# BinaryClock_Control.net
KiCad netlist of a schematic drawn in Altium Designer
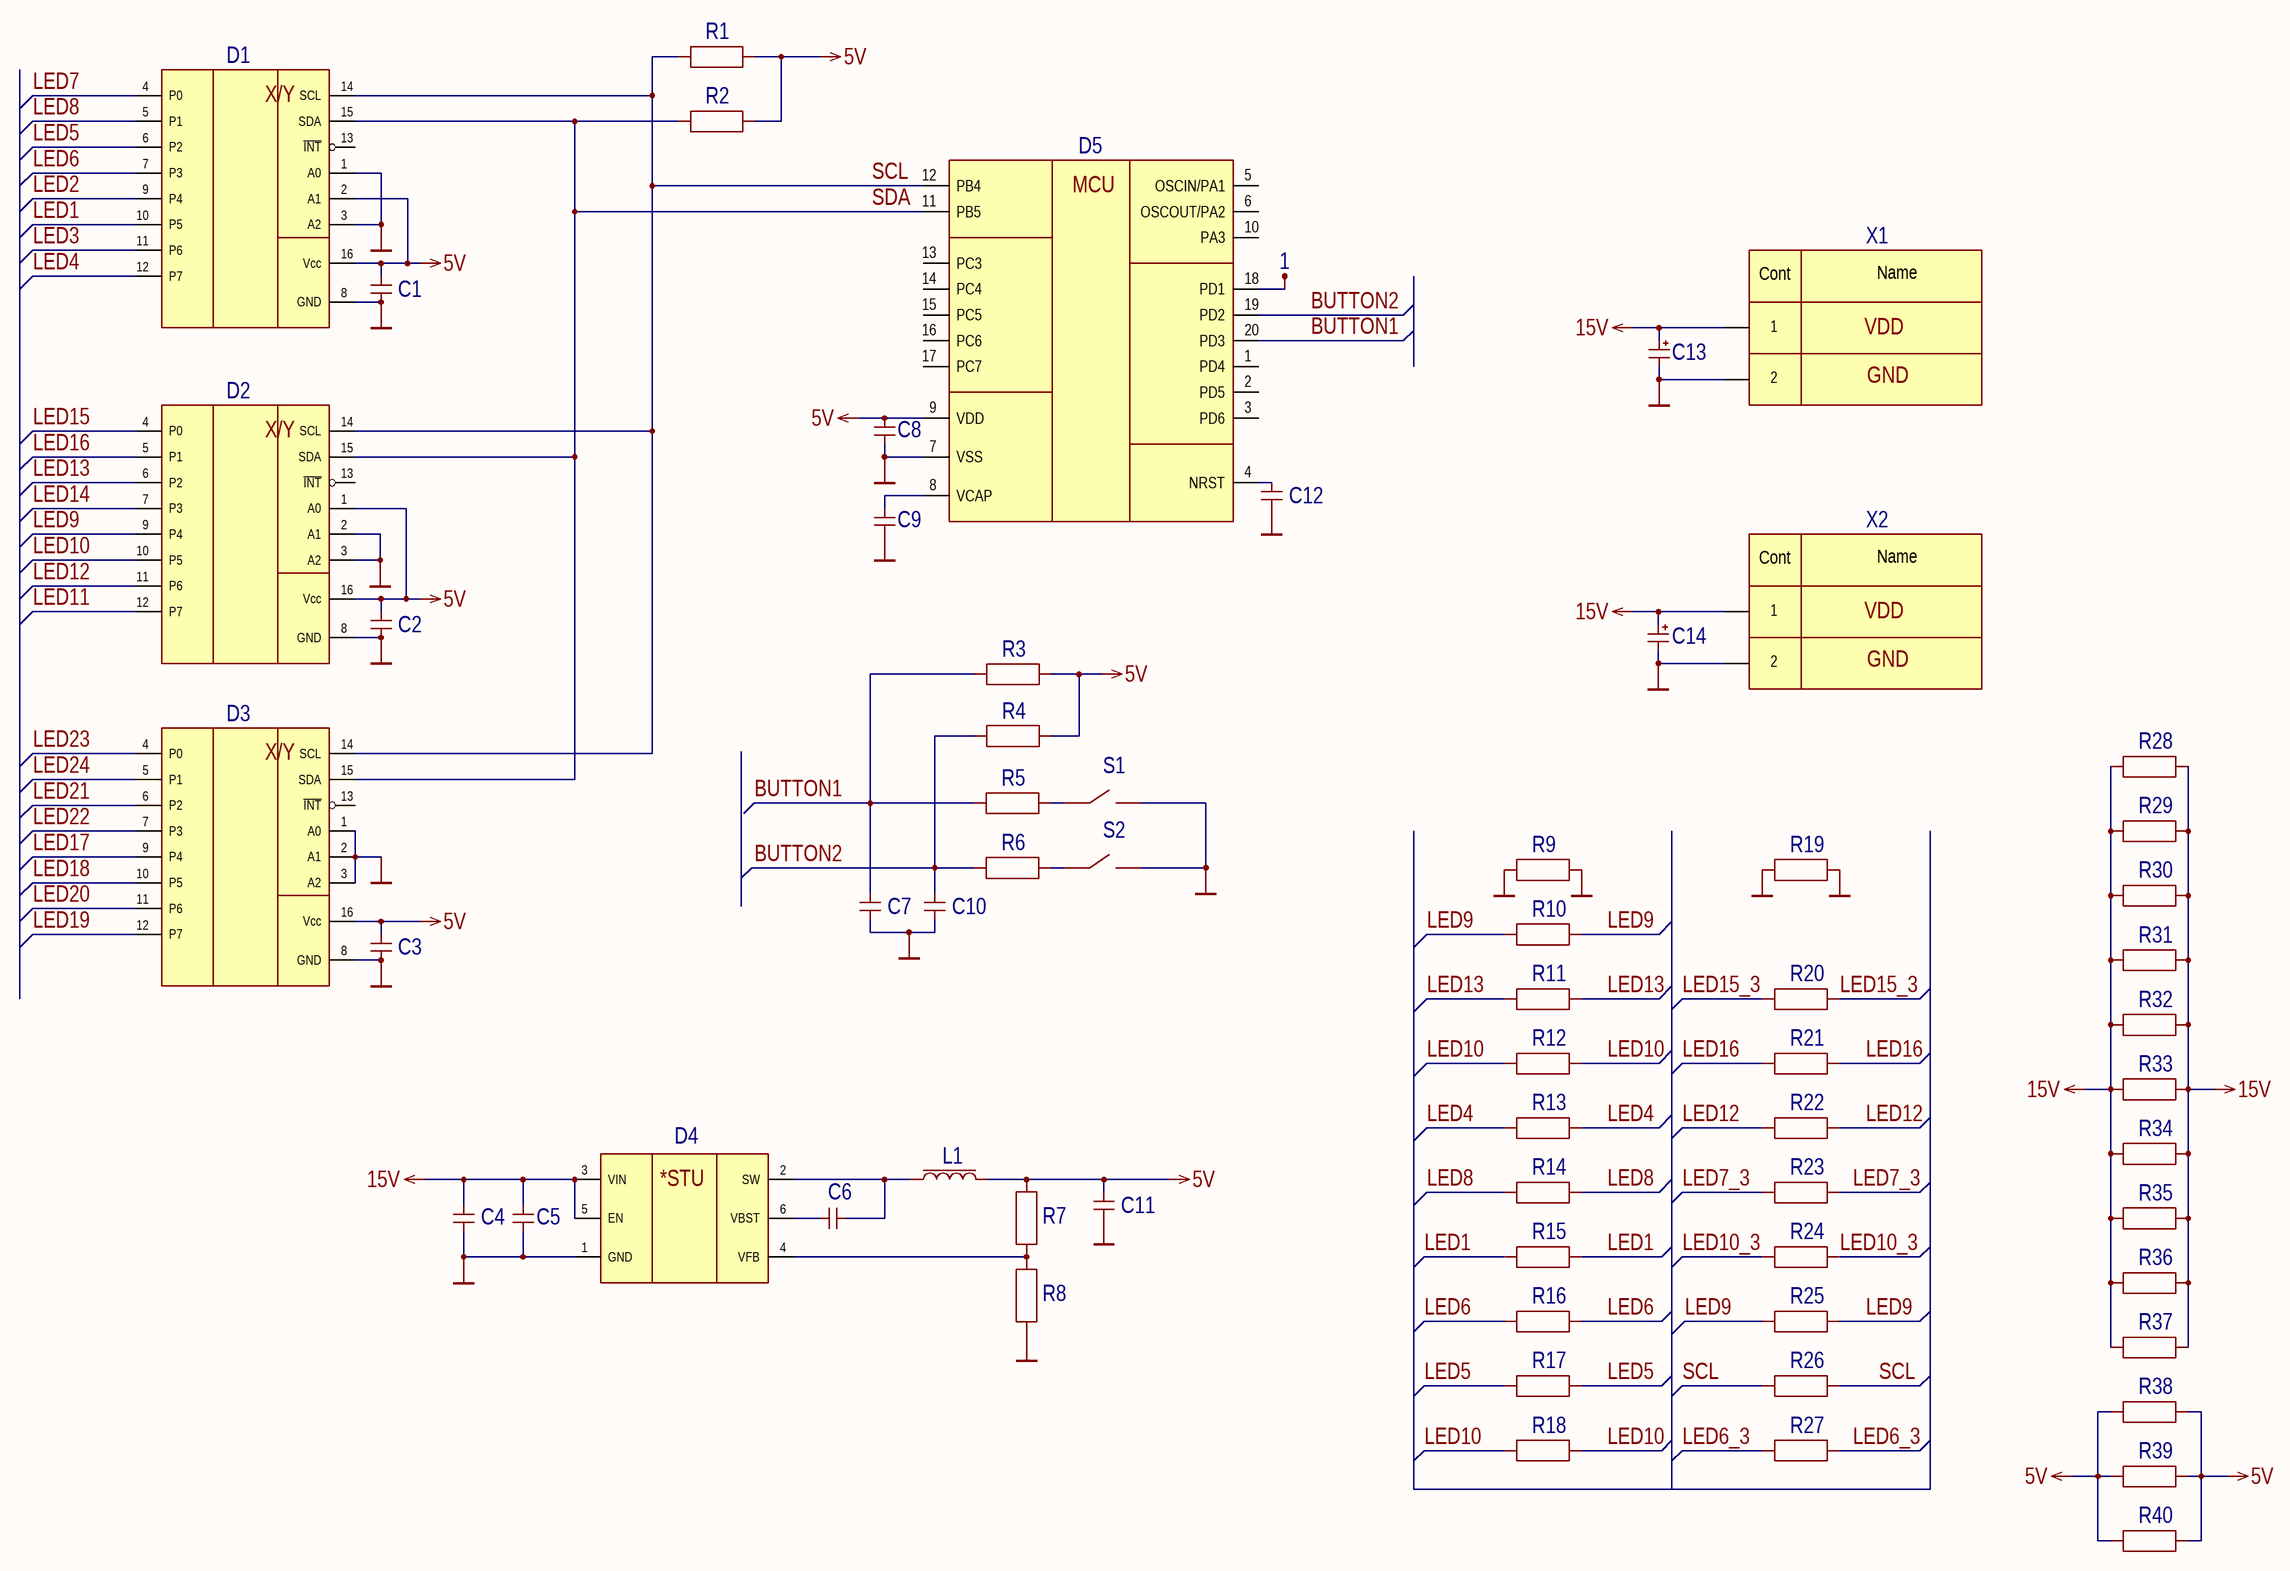
[diagram p0: BinaryClock_Control.SchDoc]

(export (version "E")
  (design (tool "Eeschema 10.0.6"))
  (components
    (comp (ref "1") (value "Point") (footprint "point") (libsource (lib "Passive,Diodes") (part "Point")))
    (comp (ref "C1")
      (value "0805-16 V-X7R-0.1uF±10 %")
      (footprint "SMD-0805C")
      (description "Capacitor")
      (fields (field (name "MANUFACTURER") "Murata"))
      (libsource (lib "Passive,Diodes") (part "Cap"))
    )
    (comp (ref "C2")
      (value "0805-16 V-X7R-0.1uF±10 %")
      (footprint "SMD-0805C")
      (description "Capacitor")
      (fields (field (name "MANUFACTURER") "Murata"))
      (libsource (lib "Passive,Diodes") (part "Cap"))
    )
    (comp (ref "C3")
      (value "0805-16 V-X7R-0.1uF±10 %")
      (footprint "SMD-0805C")
      (description "Capacitor")
      (fields (field (name "MANUFACTURER") "Murata"))
      (libsource (lib "Passive,Diodes") (part "Cap"))
    )
    (comp (ref "C4")
      (value "0805-25 V-X5R-10uF±10 %")
      (footprint "SMD-0805C")
      (description "Capacitor")
      (libsource (lib "Passive,Diodes") (part "Cap"))
    )
    (comp (ref "C5")
      (value "0805-50 V-X7R-0.1uF±10 %")
      (footprint "SMD-0805C")
      (description "Capacitor")
      (libsource (lib "Passive,Diodes") (part "Cap"))
    )
    (comp (ref "C6")
      (value "0805-16 V-X7R-0.1uF±10 %")
      (footprint "SMD-0805C")
      (description "Capacitor")
      (fields (field (name "MANUFACTURER") "Murata"))
      (libsource (lib "Passive,Diodes") (part "Cap"))
    )
    (comp (ref "C7")
      (value "0805-16 V-X7R-0.1uF±10 %")
      (footprint "SMD-0805C")
      (description "Capacitor")
      (fields (field (name "MANUFACTURER") "Murata"))
      (libsource (lib "Passive,Diodes") (part "Cap"))
    )
    (comp (ref "C8")
      (value "0805-16 V-X7R-0.1uF±10 %")
      (footprint "SMD-0805C")
      (description "Capacitor")
      (fields (field (name "MANUFACTURER") "Murata"))
      (libsource (lib "Passive,Diodes") (part "Cap"))
    )
    (comp (ref "C9")
      (value "0805-16 V-X7R-1uF±10 %")
      (footprint "SMD-0805C")
      (description "Capacitor")
      (fields (field (name "MANUFACTURER") "Murata"))
      (libsource (lib "Passive,Diodes") (part "Cap"))
    )
    (comp (ref "C10")
      (value "0805-16 V-X7R-0.1uF±10 %")
      (footprint "SMD-0805C")
      (description "Capacitor")
      (fields (field (name "MANUFACTURER") "Murata"))
      (libsource (lib "Passive,Diodes") (part "Cap"))
    )
    (comp (ref "C11")
      (value "1206-16 V-X7R-22uF±10 %")
      (footprint "SMD-1206C")
      (description "Capacitor")
      (libsource (lib "Passive,Diodes") (part "Cap"))
    )
    (comp (ref "C12")
      (value "0805-16 V-X7R-0.1uF±10 %")
      (footprint "SMD-0805C")
      (description "Capacitor")
      (fields (field (name "MANUFACTURER") "Murata"))
      (libsource (lib "Passive,Diodes") (part "Cap"))
    )
    (comp (ref "C13")
      (value "10x10.5-50 V-100 uF±20 %")
      (footprint "CAP_10x10.5")
      (description "Electrolytic capacitor")
      (libsource (lib "Passive,Diodes") (part "Cap_el"))
    )
    (comp (ref "C14")
      (value "10x10.5-50 V-100 uF±20 %")
      (footprint "CAP_10x10.5")
      (description "Electrolytic capacitor")
      (libsource (lib "Passive,Diodes") (part "Cap_el"))
    )
    (comp (ref "D1")
      (value "PCF8574T/3.512")
      (footprint "SO-16")
      (description "Remote 8-bit I/O expander for I2C bus")
      (fields (field (name "MANUFACTURER") "NXP"))
      (libsource (lib "Devices") (part "PCF8574"))
    )
    (comp (ref "D2")
      (value "PCF8574T/3.512")
      (footprint "SO-16")
      (description "Remote 8-bit I/O expander for I2C bus")
      (fields (field (name "MANUFACTURER") "NXP"))
      (libsource (lib "Devices") (part "PCF8574"))
    )
    (comp (ref "D3")
      (value "PCF8574T/3.512")
      (footprint "SO-16")
      (description "Remote 8-bit I/O expander for I2C bus")
      (fields (field (name "MANUFACTURER") "NXP"))
      (libsource (lib "Devices") (part "PCF8574"))
    )
    (comp (ref "D4")
      (value "TPS562200DDCT")
      (footprint "SOT23-6_M")
      (description "4.5-V To 17-V Input, 2-A, 3-A Synchronous Step-Down Voltage Regulator")
      (fields (field (name "MANUFACTURER") "Texas Instruments"))
      (libsource (lib "Devices") (part "TPS562200"))
    )
    (comp (ref "D5")
      (value "STM8S103F3P6")
      (footprint "TSSOP-20")
      (fields (field (name "MANUFACTURER") "STMicroelectronics"))
      (libsource (lib "Devices") (part "STM8S103FxP"))
    )
    (comp (ref "L1")
      (value "NLCV32T-4R7M-EF")
      (footprint "1210_M")
      (description "Inductor")
      (fields (field (name "MANUFACTURER") "TDK"))
      (libsource (lib "Passive,Diodes") (part "Inductor"))
    )
    (comp (ref "R1")
      (value "0805±5 %-10 kOhm")
      (footprint "SMD-0805-RES")
      (description "Resistor")
      (libsource (lib "Passive,Diodes") (part "Res"))
    )
    (comp (ref "R2")
      (value "0805±5 %-10 kOhm")
      (footprint "SMD-0805-RES")
      (description "Resistor")
      (libsource (lib "Passive,Diodes") (part "Res"))
    )
    (comp (ref "R3")
      (value "0805±5 %-10 kOhm")
      (footprint "SMD-0805-RES")
      (description "Resistor")
      (libsource (lib "Passive,Diodes") (part "Res"))
    )
    (comp (ref "R4")
      (value "0805±5 %-10 kOhm")
      (footprint "SMD-0805-RES")
      (description "Resistor")
      (libsource (lib "Passive,Diodes") (part "Res"))
    )
    (comp (ref "R5")
      (value "0805±5 %-100 Ohm")
      (footprint "SMD-0805-RES")
      (description "Resistor")
      (libsource (lib "Passive,Diodes") (part "Res"))
    )
    (comp (ref "R6")
      (value "0805±5 %-100 Ohm")
      (footprint "SMD-0805-RES")
      (description "Resistor")
      (libsource (lib "Passive,Diodes") (part "Res"))
    )
    (comp (ref "R7")
      (value "0805±1 %-110 kOhm")
      (footprint "SMD-0805-RES")
      (description "Resistor")
      (libsource (lib "Passive,Diodes") (part "Res"))
    )
    (comp (ref "R8")
      (value "0805±1 %-20 kOhm")
      (footprint "SMD-0805-RES")
      (description "Resistor")
      (libsource (lib "Passive,Diodes") (part "Res"))
    )
    (comp (ref "R9")
      (value "1206±5 %-0 Ohm")
      (footprint "R1206")
      (description "Resistor")
      (libsource (lib "Passive,Diodes") (part "Res"))
    )
    (comp (ref "R10")
      (value "1206±5 %-0 Ohm")
      (footprint "R1206")
      (description "Resistor")
      (libsource (lib "Passive,Diodes") (part "Res"))
    )
    (comp (ref "R11")
      (value "1206±5 %-0 Ohm")
      (footprint "R1206")
      (description "Resistor")
      (libsource (lib "Passive,Diodes") (part "Res"))
    )
    (comp (ref "R12")
      (value "1206±5 %-0 Ohm")
      (footprint "R1206")
      (description "Resistor")
      (libsource (lib "Passive,Diodes") (part "Res"))
    )
    (comp (ref "R13")
      (value "1206±5 %-0 Ohm")
      (footprint "R1206")
      (description "Resistor")
      (libsource (lib "Passive,Diodes") (part "Res"))
    )
    (comp (ref "R14")
      (value "1206±5 %-0 Ohm")
      (footprint "R1206")
      (description "Resistor")
      (libsource (lib "Passive,Diodes") (part "Res"))
    )
    (comp (ref "R15")
      (value "1206±5 %-0 Ohm")
      (footprint "R1206")
      (description "Resistor")
      (libsource (lib "Passive,Diodes") (part "Res"))
    )
    (comp (ref "R16")
      (value "1206±5 %-0 Ohm")
      (footprint "R1206")
      (description "Resistor")
      (libsource (lib "Passive,Diodes") (part "Res"))
    )
    (comp (ref "R17")
      (value "1206±5 %-0 Ohm")
      (footprint "R1206")
      (description "Resistor")
      (libsource (lib "Passive,Diodes") (part "Res"))
    )
    (comp (ref "R18")
      (value "1206±5 %-0 Ohm")
      (footprint "R1206")
      (description "Resistor")
      (libsource (lib "Passive,Diodes") (part "Res"))
    )
    (comp (ref "R19")
      (value "1206±5 %-0 Ohm")
      (footprint "R1206")
      (description "Resistor")
      (libsource (lib "Passive,Diodes") (part "Res"))
    )
    (comp (ref "R20")
      (value "1206±5 %-0 Ohm")
      (footprint "R1206")
      (description "Resistor")
      (libsource (lib "Passive,Diodes") (part "Res"))
    )
    (comp (ref "R21")
      (value "1206±5 %-0 Ohm")
      (footprint "R1206")
      (description "Resistor")
      (libsource (lib "Passive,Diodes") (part "Res"))
    )
    (comp (ref "R22")
      (value "1206±5 %-0 Ohm")
      (footprint "R1206")
      (description "Resistor")
      (libsource (lib "Passive,Diodes") (part "Res"))
    )
    (comp (ref "R23")
      (value "1206±5 %-0 Ohm")
      (footprint "R1206")
      (description "Resistor")
      (libsource (lib "Passive,Diodes") (part "Res"))
    )
    (comp (ref "R24")
      (value "1206±5 %-0 Ohm")
      (footprint "R1206")
      (description "Resistor")
      (libsource (lib "Passive,Diodes") (part "Res"))
    )
    (comp (ref "R25")
      (value "1206±5 %-0 Ohm")
      (footprint "R1206")
      (description "Resistor")
      (libsource (lib "Passive,Diodes") (part "Res"))
    )
    (comp (ref "R26")
      (value "1206±5 %-0 Ohm")
      (footprint "R1206")
      (description "Resistor")
      (libsource (lib "Passive,Diodes") (part "Res"))
    )
    (comp (ref "R27")
      (value "1206±5 %-0 Ohm")
      (footprint "R1206")
      (description "Resistor")
      (libsource (lib "Passive,Diodes") (part "Res"))
    )
    (comp (ref "R28")
      (value "1206±5 %-0 Ohm")
      (footprint "R1206")
      (description "Resistor")
      (libsource (lib "Passive,Diodes") (part "Res"))
    )
    (comp (ref "R29")
      (value "1206±5 %-0 Ohm")
      (footprint "R1206")
      (description "Resistor")
      (libsource (lib "Passive,Diodes") (part "Res"))
    )
    (comp (ref "R30")
      (value "1206±5 %-0 Ohm")
      (footprint "R1206")
      (description "Resistor")
      (libsource (lib "Passive,Diodes") (part "Res"))
    )
    (comp (ref "R31")
      (value "1206±5 %-0 Ohm")
      (footprint "R1206")
      (description "Resistor")
      (libsource (lib "Passive,Diodes") (part "Res"))
    )
    (comp (ref "R32")
      (value "1206±5 %-0 Ohm")
      (footprint "R1206")
      (description "Resistor")
      (libsource (lib "Passive,Diodes") (part "Res"))
    )
    (comp (ref "R33")
      (value "1206±5 %-0 Ohm")
      (footprint "R1206")
      (description "Resistor")
      (libsource (lib "Passive,Diodes") (part "Res"))
    )
    (comp (ref "R34")
      (value "1206±5 %-0 Ohm")
      (footprint "R1206")
      (description "Resistor")
      (libsource (lib "Passive,Diodes") (part "Res"))
    )
    (comp (ref "R35")
      (value "1206±5 %-0 Ohm")
      (footprint "R1206")
      (description "Resistor")
      (libsource (lib "Passive,Diodes") (part "Res"))
    )
    (comp (ref "R36")
      (value "1206±5 %-0 Ohm")
      (footprint "R1206")
      (description "Resistor")
      (libsource (lib "Passive,Diodes") (part "Res"))
    )
    (comp (ref "R37")
      (value "1206±5 %-0 Ohm")
      (footprint "R1206")
      (description "Resistor")
      (libsource (lib "Passive,Diodes") (part "Res"))
    )
    (comp (ref "R38")
      (value "1206±5 %-0 Ohm")
      (footprint "R1206")
      (description "Resistor")
      (libsource (lib "Passive,Diodes") (part "Res"))
    )
    (comp (ref "R39")
      (value "1206±5 %-0 Ohm")
      (footprint "R1206")
      (description "Resistor")
      (libsource (lib "Passive,Diodes") (part "Res"))
    )
    (comp (ref "R40")
      (value "1206±5 %-0 Ohm")
      (footprint "R1206")
      (description "Resistor")
      (libsource (lib "Passive,Diodes") (part "Res"))
    )
    (comp (ref "S1")
      (value "1243SHIM-160G-G")
      (footprint "1243S")
      (description "Tact button SPST")
      (fields (field (name "MANUFACTURER") "Switronic"))
      (libsource (lib "Connectors") (part "button"))
    )
    (comp (ref "S2")
      (value "1243SHIM-160G-G")
      (footprint "1243S")
      (description "Tact button SPST")
      (fields (field (name "MANUFACTURER") "Switronic"))
      (libsource (lib "Connectors") (part "button"))
    )
    (comp (ref "X1")
      (value "DC-005-5A-2.5-SMT")
      (footprint "PJ_2.5MM_SMT")
      (description "Power jack 2.5 mm SMT connector")
      (libsource (lib "Connectors") (part "Power_Jack_SMT_2.5mm"))
    )
    (comp (ref "X2")
      (value "DC-005-5A-2.5-SMT")
      (footprint "PJ_2.5MM_SMT")
      (description "Power jack 2.5 mm SMT connector")
      (libsource (lib "Connectors") (part "Power_Jack_SMT_2.5mm"))
    )
  )
  (nets
    (net (code "1") (name "/BUTTON1") (class "Default")
      (node (ref "C7") (pin "2") (pinfunction "2_2") (pintype "passive"))
      (node (ref "D5") (pin "20") (pinfunction "PD3_20") (pintype "passive"))
      (node (ref "R3") (pin "1") (pinfunction "1_1") (pintype "passive"))
      (node (ref "R5") (pin "1") (pinfunction "1_1") (pintype "passive"))
    )
    (net (code "2") (name "/BUTTON2") (class "Default")
      (node (ref "C10") (pin "2") (pinfunction "2_2") (pintype "passive"))
      (node (ref "D5") (pin "19") (pinfunction "PD2_19") (pintype "passive"))
      (node (ref "R4") (pin "1") (pinfunction "1_1") (pintype "passive"))
      (node (ref "R6") (pin "1") (pinfunction "1_1") (pintype "passive"))
    )
    (net (code "3") (name "/LED1") (class "Default")
      (node (ref "D1") (pin "10") (pinfunction "P5_10") (pintype "passive"))
      (node (ref "R15") (pin "1") (pinfunction "1_1") (pintype "passive"))
      (node (ref "R15") (pin "2") (pinfunction "2_2") (pintype "passive"))
    )
    (net (code "4") (name "/LED2") (class "Default")
      (node (ref "D1") (pin "9") (pinfunction "P4_9") (pintype "passive"))
    )
    (net (code "5") (name "/LED3") (class "Default")
      (node (ref "D1") (pin "11") (pinfunction "P6_11") (pintype "passive"))
    )
    (net (code "6") (name "/LED4") (class "Default")
      (node (ref "D1") (pin "12") (pinfunction "P7_12") (pintype "passive"))
      (node (ref "R13") (pin "1") (pinfunction "1_1") (pintype "passive"))
      (node (ref "R13") (pin "2") (pinfunction "2_2") (pintype "passive"))
    )
    (net (code "7") (name "/LED5") (class "Default")
      (node (ref "D1") (pin "6") (pinfunction "P2_6") (pintype "passive"))
      (node (ref "R17") (pin "1") (pinfunction "1_1") (pintype "passive"))
      (node (ref "R17") (pin "2") (pinfunction "2_2") (pintype "passive"))
    )
    (net (code "8") (name "/LED6") (class "Default")
      (node (ref "D1") (pin "7") (pinfunction "P3_7") (pintype "passive"))
      (node (ref "R16") (pin "1") (pinfunction "1_1") (pintype "passive"))
      (node (ref "R16") (pin "2") (pinfunction "2_2") (pintype "passive"))
    )
    (net (code "9") (name "/LED6_3") (class "Default")
      (node (ref "R27") (pin "1") (pinfunction "1_1") (pintype "passive"))
      (node (ref "R27") (pin "2") (pinfunction "2_2") (pintype "passive"))
    )
    (net (code "10") (name "/LED7") (class "Default")
      (node (ref "D1") (pin "4") (pinfunction "P0_4") (pintype "passive"))
    )
    (net (code "11") (name "/LED7_3") (class "Default")
      (node (ref "R23") (pin "1") (pinfunction "1_1") (pintype "passive"))
      (node (ref "R23") (pin "2") (pinfunction "2_2") (pintype "passive"))
    )
    (net (code "12") (name "/LED8") (class "Default")
      (node (ref "D1") (pin "5") (pinfunction "P1_5") (pintype "passive"))
      (node (ref "R14") (pin "1") (pinfunction "1_1") (pintype "passive"))
      (node (ref "R14") (pin "2") (pinfunction "2_2") (pintype "passive"))
    )
    (net (code "13") (name "/LED9") (class "Default")
      (node (ref "D2") (pin "9") (pinfunction "P4_9") (pintype "passive"))
      (node (ref "R10") (pin "1") (pinfunction "1_1") (pintype "passive"))
      (node (ref "R10") (pin "2") (pinfunction "2_2") (pintype "passive"))
      (node (ref "R25") (pin "1") (pinfunction "1_1") (pintype "passive"))
      (node (ref "R25") (pin "2") (pinfunction "2_2") (pintype "passive"))
    )
    (net (code "14") (name "/LED10") (class "Default")
      (node (ref "D2") (pin "10") (pinfunction "P5_10") (pintype "passive"))
      (node (ref "R12") (pin "1") (pinfunction "1_1") (pintype "passive"))
      (node (ref "R12") (pin "2") (pinfunction "2_2") (pintype "passive"))
      (node (ref "R18") (pin "1") (pinfunction "1_1") (pintype "passive"))
      (node (ref "R18") (pin "2") (pinfunction "2_2") (pintype "passive"))
    )
    (net (code "15") (name "/LED10_3") (class "Default")
      (node (ref "R24") (pin "1") (pinfunction "1_1") (pintype "passive"))
      (node (ref "R24") (pin "2") (pinfunction "2_2") (pintype "passive"))
    )
    (net (code "16") (name "/LED11") (class "Default")
      (node (ref "D2") (pin "12") (pinfunction "P7_12") (pintype "passive"))
    )
    (net (code "17") (name "/LED12") (class "Default")
      (node (ref "D2") (pin "11") (pinfunction "P6_11") (pintype "passive"))
      (node (ref "R22") (pin "1") (pinfunction "1_1") (pintype "passive"))
      (node (ref "R22") (pin "2") (pinfunction "2_2") (pintype "passive"))
    )
    (net (code "18") (name "/LED13") (class "Default")
      (node (ref "D2") (pin "6") (pinfunction "P2_6") (pintype "passive"))
      (node (ref "R11") (pin "1") (pinfunction "1_1") (pintype "passive"))
      (node (ref "R11") (pin "2") (pinfunction "2_2") (pintype "passive"))
    )
    (net (code "19") (name "/LED14") (class "Default")
      (node (ref "D2") (pin "7") (pinfunction "P3_7") (pintype "passive"))
    )
    (net (code "20") (name "/LED15") (class "Default")
      (node (ref "D2") (pin "4") (pinfunction "P0_4") (pintype "passive"))
    )
    (net (code "21") (name "/LED15_3") (class "Default")
      (node (ref "R20") (pin "1") (pinfunction "1_1") (pintype "passive"))
      (node (ref "R20") (pin "2") (pinfunction "2_2") (pintype "passive"))
    )
    (net (code "22") (name "/LED16") (class "Default")
      (node (ref "D2") (pin "5") (pinfunction "P1_5") (pintype "passive"))
      (node (ref "R21") (pin "1") (pinfunction "1_1") (pintype "passive"))
      (node (ref "R21") (pin "2") (pinfunction "2_2") (pintype "passive"))
    )
    (net (code "23") (name "/LED17") (class "Default")
      (node (ref "D3") (pin "9") (pinfunction "P4_9") (pintype "passive"))
    )
    (net (code "24") (name "/LED18") (class "Default")
      (node (ref "D3") (pin "10") (pinfunction "P5_10") (pintype "passive"))
    )
    (net (code "25") (name "/LED19") (class "Default")
      (node (ref "D3") (pin "12") (pinfunction "P7_12") (pintype "passive"))
    )
    (net (code "26") (name "/LED20") (class "Default")
      (node (ref "D3") (pin "11") (pinfunction "P6_11") (pintype "passive"))
    )
    (net (code "27") (name "/LED21") (class "Default")
      (node (ref "D3") (pin "6") (pinfunction "P2_6") (pintype "passive"))
    )
    (net (code "28") (name "/LED22") (class "Default")
      (node (ref "D3") (pin "7") (pinfunction "P3_7") (pintype "passive"))
    )
    (net (code "29") (name "/LED23") (class "Default")
      (node (ref "D3") (pin "4") (pinfunction "P0_4") (pintype "passive"))
    )
    (net (code "30") (name "/LED24") (class "Default")
      (node (ref "D3") (pin "5") (pinfunction "P1_5") (pintype "passive"))
    )
    (net (code "31") (name "/SCL") (class "Default")
      (node (ref "D1") (pin "14") (pinfunction "SCL_14") (pintype "passive"))
      (node (ref "D2") (pin "14") (pinfunction "SCL_14") (pintype "passive"))
      (node (ref "D3") (pin "14") (pinfunction "SCL_14") (pintype "passive"))
      (node (ref "D5") (pin "12") (pinfunction "PB4_12") (pintype "passive"))
      (node (ref "R1") (pin "1") (pinfunction "1_1") (pintype "passive"))
      (node (ref "R26") (pin "1") (pinfunction "1_1") (pintype "passive"))
      (node (ref "R26") (pin "2") (pinfunction "2_2") (pintype "passive"))
    )
    (net (code "32") (name "/SDA") (class "Default")
      (node (ref "D1") (pin "15") (pinfunction "SDA_15") (pintype "passive"))
      (node (ref "D2") (pin "15") (pinfunction "SDA_15") (pintype "passive"))
      (node (ref "D3") (pin "15") (pinfunction "SDA_15") (pintype "passive"))
      (node (ref "D5") (pin "11") (pinfunction "PB5_11") (pintype "passive"))
      (node (ref "R2") (pin "1") (pinfunction "1_1") (pintype "passive"))
    )
    (net (code "33") (name "5V") (class "Default")
      (node (ref "C1") (pin "2") (pinfunction "2_2") (pintype "passive"))
      (node (ref "C11") (pin "2") (pinfunction "2_2") (pintype "passive"))
      (node (ref "C2") (pin "2") (pinfunction "2_2") (pintype "passive"))
      (node (ref "C3") (pin "2") (pinfunction "2_2") (pintype "passive"))
      (node (ref "C8") (pin "2") (pinfunction "2_2") (pintype "passive"))
      (node (ref "D1") (pin "16") (pinfunction "Vcc_16") (pintype "power_in"))
      (node (ref "D1") (pin "2") (pinfunction "A1_2") (pintype "passive"))
      (node (ref "D2") (pin "1") (pinfunction "A0_1") (pintype "passive"))
      (node (ref "D2") (pin "16") (pinfunction "Vcc_16") (pintype "power_in"))
      (node (ref "D3") (pin "16") (pinfunction "Vcc_16") (pintype "power_in"))
      (node (ref "D5") (pin "9") (pinfunction "VDD_9") (pintype "power_in"))
      (node (ref "L1") (pin "2") (pinfunction "2_2") (pintype "passive"))
      (node (ref "R1") (pin "2") (pinfunction "2_2") (pintype "passive"))
      (node (ref "R2") (pin "2") (pinfunction "2_2") (pintype "passive"))
      (node (ref "R3") (pin "2") (pinfunction "2_2") (pintype "passive"))
      (node (ref "R38") (pin "1") (pinfunction "1_1") (pintype "passive"))
      (node (ref "R38") (pin "2") (pinfunction "2_2") (pintype "passive"))
      (node (ref "R39") (pin "1") (pinfunction "1_1") (pintype "passive"))
      (node (ref "R39") (pin "2") (pinfunction "2_2") (pintype "passive"))
      (node (ref "R4") (pin "2") (pinfunction "2_2") (pintype "passive"))
      (node (ref "R40") (pin "1") (pinfunction "1_1") (pintype "passive"))
      (node (ref "R40") (pin "2") (pinfunction "2_2") (pintype "passive"))
      (node (ref "R7") (pin "2") (pinfunction "2_2") (pintype "passive"))
    )
    (net (code "34") (name "15V") (class "Default")
      (node (ref "C13") (pin "1") (pinfunction "1_1") (pintype "passive"))
      (node (ref "C14") (pin "1") (pinfunction "1_1") (pintype "passive"))
      (node (ref "C4") (pin "2") (pinfunction "2_2") (pintype "passive"))
      (node (ref "C5") (pin "2") (pinfunction "2_2") (pintype "passive"))
      (node (ref "D4") (pin "3") (pinfunction "VIN_3") (pintype "power_in"))
      (node (ref "D4") (pin "5") (pinfunction "EN_5") (pintype "passive"))
      (node (ref "R28") (pin "1") (pinfunction "1_1") (pintype "passive"))
      (node (ref "R28") (pin "2") (pinfunction "2_2") (pintype "passive"))
      (node (ref "R29") (pin "1") (pinfunction "1_1") (pintype "passive"))
      (node (ref "R29") (pin "2") (pinfunction "2_2") (pintype "passive"))
      (node (ref "R30") (pin "1") (pinfunction "1_1") (pintype "passive"))
      (node (ref "R30") (pin "2") (pinfunction "2_2") (pintype "passive"))
      (node (ref "R31") (pin "1") (pinfunction "1_1") (pintype "passive"))
      (node (ref "R31") (pin "2") (pinfunction "2_2") (pintype "passive"))
      (node (ref "R32") (pin "1") (pinfunction "1_1") (pintype "passive"))
      (node (ref "R32") (pin "2") (pinfunction "2_2") (pintype "passive"))
      (node (ref "R33") (pin "1") (pinfunction "1_1") (pintype "passive"))
      (node (ref "R33") (pin "2") (pinfunction "2_2") (pintype "passive"))
      (node (ref "R34") (pin "1") (pinfunction "1_1") (pintype "passive"))
      (node (ref "R34") (pin "2") (pinfunction "2_2") (pintype "passive"))
      (node (ref "R35") (pin "1") (pinfunction "1_1") (pintype "passive"))
      (node (ref "R35") (pin "2") (pinfunction "2_2") (pintype "passive"))
      (node (ref "R36") (pin "1") (pinfunction "1_1") (pintype "passive"))
      (node (ref "R36") (pin "2") (pinfunction "2_2") (pintype "passive"))
      (node (ref "R37") (pin "1") (pinfunction "1_1") (pintype "passive"))
      (node (ref "R37") (pin "2") (pinfunction "2_2") (pintype "passive"))
      (node (ref "X1") (pin "1") (pinfunction "1_1") (pintype "passive"))
      (node (ref "X2") (pin "1") (pinfunction "1_1") (pintype "passive"))
    )
    (net (code "35") (name "GND") (class "Default")
      (node (ref "C1") (pin "1") (pinfunction "1_1") (pintype "passive"))
      (node (ref "C10") (pin "1") (pinfunction "1_1") (pintype "passive"))
      (node (ref "C11") (pin "1") (pinfunction "1_1") (pintype "passive"))
      (node (ref "C12") (pin "1") (pinfunction "1_1") (pintype "passive"))
      (node (ref "C13") (pin "2") (pinfunction "2_2") (pintype "passive"))
      (node (ref "C14") (pin "2") (pinfunction "2_2") (pintype "passive"))
      (node (ref "C2") (pin "1") (pinfunction "1_1") (pintype "passive"))
      (node (ref "C3") (pin "1") (pinfunction "1_1") (pintype "passive"))
      (node (ref "C4") (pin "1") (pinfunction "1_1") (pintype "passive"))
      (node (ref "C5") (pin "1") (pinfunction "1_1") (pintype "passive"))
      (node (ref "C7") (pin "1") (pinfunction "1_1") (pintype "passive"))
      (node (ref "C8") (pin "1") (pinfunction "1_1") (pintype "passive"))
      (node (ref "C9") (pin "1") (pinfunction "1_1") (pintype "passive"))
      (node (ref "D1") (pin "1") (pinfunction "A0_1") (pintype "passive"))
      (node (ref "D1") (pin "3") (pinfunction "A2_3") (pintype "passive"))
      (node (ref "D1") (pin "8") (pinfunction "GND_8") (pintype "power_in"))
      (node (ref "D2") (pin "2") (pinfunction "A1_2") (pintype "passive"))
      (node (ref "D2") (pin "3") (pinfunction "A2_3") (pintype "passive"))
      (node (ref "D2") (pin "8") (pinfunction "GND_8") (pintype "power_in"))
      (node (ref "D3") (pin "1") (pinfunction "A0_1") (pintype "passive"))
      (node (ref "D3") (pin "2") (pinfunction "A1_2") (pintype "passive"))
      (node (ref "D3") (pin "3") (pinfunction "A2_3") (pintype "passive"))
      (node (ref "D3") (pin "8") (pinfunction "GND_8") (pintype "power_in"))
      (node (ref "D4") (pin "1") (pinfunction "GND_1") (pintype "power_in"))
      (node (ref "D5") (pin "7") (pinfunction "VSS_7") (pintype "power_in"))
      (node (ref "R19") (pin "1") (pinfunction "1_1") (pintype "passive"))
      (node (ref "R19") (pin "2") (pinfunction "2_2") (pintype "passive"))
      (node (ref "R8") (pin "1") (pinfunction "1_1") (pintype "passive"))
      (node (ref "R9") (pin "1") (pinfunction "1_1") (pintype "passive"))
      (node (ref "R9") (pin "2") (pinfunction "2_2") (pintype "passive"))
      (node (ref "S1") (pin "2") (pinfunction "2_2") (pintype "passive"))
      (node (ref "S2") (pin "2") (pinfunction "2_2") (pintype "passive"))
      (node (ref "X1") (pin "2") (pinfunction "2_2") (pintype "passive"))
      (node (ref "X2") (pin "2") (pinfunction "2_2") (pintype "passive"))
    )
    (net (code "36") (name "Net-(D4-SW)") (class "Default")
      (node (ref "C6") (pin "1") (pinfunction "1_1") (pintype "passive"))
      (node (ref "D4") (pin "2") (pinfunction "SW_2") (pintype "passive"))
      (node (ref "L1") (pin "1") (pinfunction "1_1") (pintype "passive"))
    )
    (net (code "37") (name "Net-(D4-VBST)") (class "Default")
      (node (ref "C6") (pin "2") (pinfunction "2_2") (pintype "passive"))
      (node (ref "D4") (pin "6") (pinfunction "VBST_6") (pintype "passive"))
    )
    (net (code "38") (name "Net-(D4-VFB)") (class "Default")
      (node (ref "D4") (pin "4") (pinfunction "VFB_4") (pintype "passive"))
      (node (ref "R7") (pin "1") (pinfunction "1_1") (pintype "passive"))
      (node (ref "R8") (pin "2") (pinfunction "2_2") (pintype "passive"))
    )
    (net (code "39") (name "Net-(D5-NRST)") (class "Default")
      (node (ref "C12") (pin "2") (pinfunction "2_2") (pintype "passive"))
      (node (ref "D5") (pin "4") (pinfunction "NRST_4") (pintype "passive"))
    )
    (net (code "40") (name "Net-(D5-PD1)") (class "Default")
      (node (ref "1") (pin "1") (pintype "passive"))
      (node (ref "D5") (pin "18") (pinfunction "PD1_18") (pintype "passive"))
    )
    (net (code "41") (name "Net-(D5-VCAP)") (class "Default")
      (node (ref "C9") (pin "2") (pinfunction "2_2") (pintype "passive"))
      (node (ref "D5") (pin "8") (pinfunction "VCAP_8") (pintype "passive"))
    )
    (net (code "42") (name "Net-(R5-Pad2)") (class "Default")
      (node (ref "R5") (pin "2") (pinfunction "2_2") (pintype "passive"))
      (node (ref "S1") (pin "1") (pinfunction "1_1") (pintype "passive"))
    )
    (net (code "43") (name "Net-(R6-Pad2)") (class "Default")
      (node (ref "R6") (pin "2") (pinfunction "2_2") (pintype "passive"))
      (node (ref "S2") (pin "1") (pinfunction "1_1") (pintype "passive"))
    )
    (net (code "44") (name "unconnected-(D1-~{INT}-Pad13)") (class "Default")
      (node (ref "D1") (pin "13") (pinfunction "~{INT}_13") (pintype "passive"))
    )
    (net (code "45") (name "unconnected-(D2-~{INT}-Pad13)") (class "Default")
      (node (ref "D2") (pin "13") (pinfunction "~{INT}_13") (pintype "passive"))
    )
    (net (code "46") (name "unconnected-(D3-~{INT}-Pad13)") (class "Default")
      (node (ref "D3") (pin "13") (pinfunction "~{INT}_13") (pintype "passive"))
    )
    (net (code "47") (name "unconnected-(D5-OSCIN{slash}PA1-Pad5)") (class "Default")
      (node (ref "D5") (pin "5") (pinfunction "OSCIN/PA1_5") (pintype "passive"))
    )
    (net (code "48") (name "unconnected-(D5-OSCOUT{slash}PA2-Pad6)") (class "Default")
      (node (ref "D5") (pin "6") (pinfunction "OSCOUT/PA2_6") (pintype "passive"))
    )
    (net (code "49") (name "unconnected-(D5-PA3-Pad10)") (class "Default")
      (node (ref "D5") (pin "10") (pinfunction "PA3_10") (pintype "passive"))
    )
    (net (code "50") (name "unconnected-(D5-PC3-Pad13)") (class "Default")
      (node (ref "D5") (pin "13") (pinfunction "PC3_13") (pintype "passive"))
    )
    (net (code "51") (name "unconnected-(D5-PC4-Pad14)") (class "Default")
      (node (ref "D5") (pin "14") (pinfunction "PC4_14") (pintype "passive"))
    )
    (net (code "52") (name "unconnected-(D5-PC5-Pad15)") (class "Default")
      (node (ref "D5") (pin "15") (pinfunction "PC5_15") (pintype "passive"))
    )
    (net (code "53") (name "unconnected-(D5-PC6-Pad16)") (class "Default")
      (node (ref "D5") (pin "16") (pinfunction "PC6_16") (pintype "passive"))
    )
    (net (code "54") (name "unconnected-(D5-PC7-Pad17)") (class "Default")
      (node (ref "D5") (pin "17") (pinfunction "PC7_17") (pintype "passive"))
    )
    (net (code "55") (name "unconnected-(D5-PD4-Pad1)") (class "Default")
      (node (ref "D5") (pin "1") (pinfunction "PD4_1") (pintype "passive"))
    )
    (net (code "56") (name "unconnected-(D5-PD5-Pad2)") (class "Default")
      (node (ref "D5") (pin "2") (pinfunction "PD5_2") (pintype "passive"))
    )
    (net (code "57") (name "unconnected-(D5-PD6-Pad3)") (class "Default")
      (node (ref "D5") (pin "3") (pinfunction "PD6_3") (pintype "passive"))
    )
  )
)
